# I2C_nRF.net
KiCad netlist of a schematic drawn in EAGLE
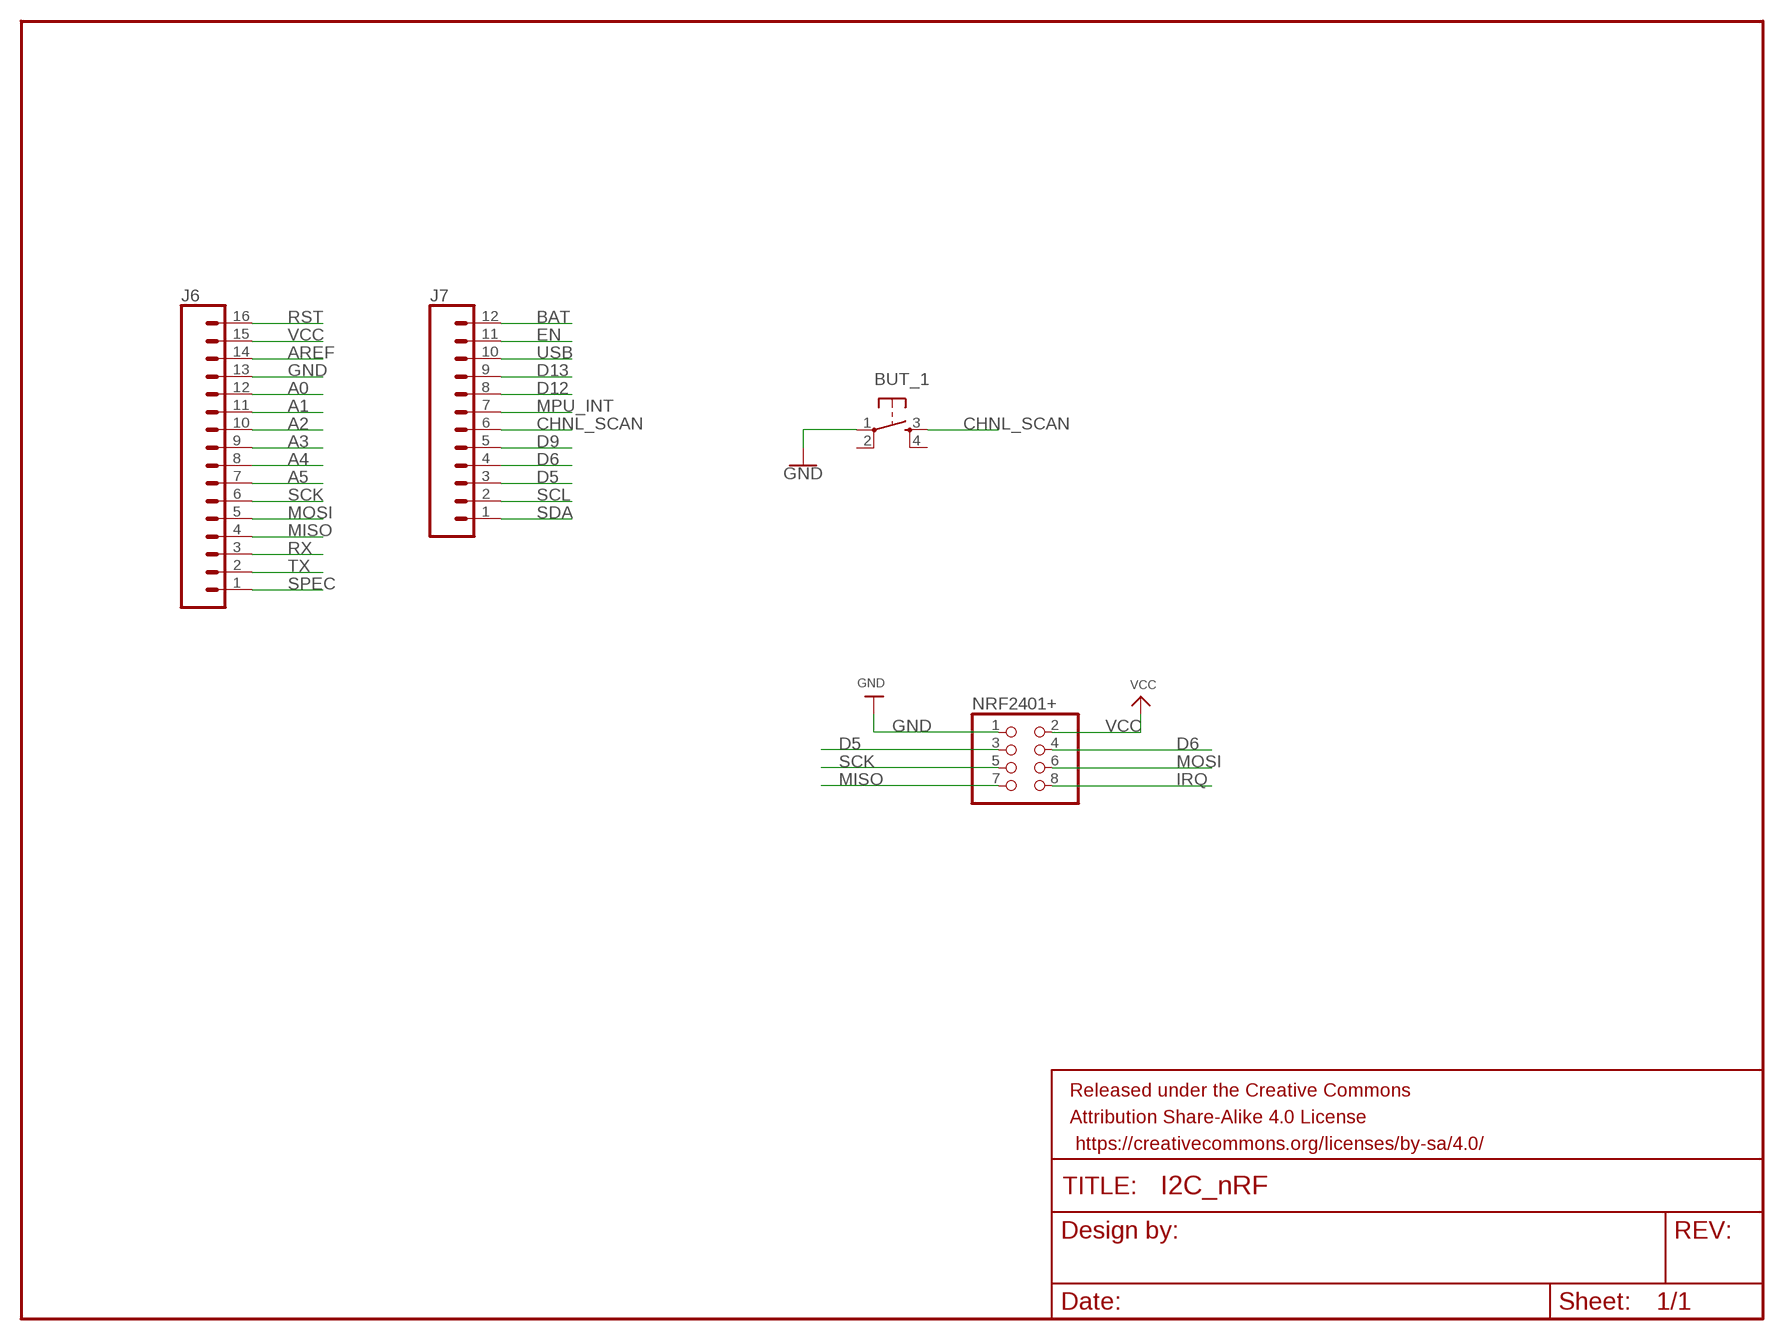
[diagram p0: schematic, sheet 1]

(export (version "E")
  (design (tool "Eeschema 10.0.6"))
  (components
    (comp (ref "BUT_1")
      (value "TAC_SWITCHPTH")
      (footprint "eagle-import:TACTILE-PTH")
      (libsource (lib "eagle-import") (part "TAC_SWITCHPTH"))
    )
    (comp (ref "FRAME1")
      (value "FRAME-LETTER")
      (footprint "eagle-import:CREATIVE_COMMONS")
      (libsource (lib "eagle-import") (part "FRAME-LETTER"))
    )
    (comp (ref "J6")
      (value "CONN_16")
      (footprint "eagle-import:1X16")
      (libsource (lib "eagle-import") (part "CONN_16"))
    )
    (comp (ref "J7")
      (value "CONN_12")
      (footprint "eagle-import:1X12")
      (libsource (lib "eagle-import") (part "CONN_12"))
    )
    (comp (ref "NRF2401+")
      (value "PINHD-2X4")
      (footprint "eagle-import:2X04")
      (libsource (lib "eagle-import") (part "PINHD-2X4"))
    )
  )
  (nets
    (net (code "1") (name "/A0") (class "Default")
      (node (ref "J6") (pin "12") (pinfunction "12_12") (pintype "passive"))
    )
    (net (code "2") (name "/A1") (class "Default")
      (node (ref "J6") (pin "11") (pinfunction "11_11") (pintype "passive"))
    )
    (net (code "3") (name "/A2") (class "Default")
      (node (ref "J6") (pin "10") (pinfunction "10_10") (pintype "passive"))
    )
    (net (code "4") (name "/A3") (class "Default")
      (node (ref "J6") (pin "9") (pinfunction "9_9") (pintype "passive"))
    )
    (net (code "5") (name "/A4") (class "Default")
      (node (ref "J6") (pin "8") (pinfunction "8_8") (pintype "passive"))
    )
    (net (code "6") (name "/A5") (class "Default")
      (node (ref "J6") (pin "7") (pinfunction "7_7") (pintype "passive"))
    )
    (net (code "7") (name "/AREF") (class "Default")
      (node (ref "J6") (pin "14") (pinfunction "14_14") (pintype "passive"))
    )
    (net (code "8") (name "/BAT") (class "Default")
      (node (ref "J7") (pin "12") (pinfunction "12_12") (pintype "passive"))
    )
    (net (code "9") (name "/CHNL_SCAN") (class "Default")
      (node (ref "BUT_1") (pin "3") (pinfunction "3_3") (pintype "passive"))
      (node (ref "J7") (pin "6") (pinfunction "6_6") (pintype "passive"))
    )
    (net (code "10") (name "/D5") (class "Default")
      (node (ref "J7") (pin "3") (pinfunction "3_3") (pintype "passive"))
      (node (ref "NRF2401+") (pin "3") (pinfunction "3_3") (pintype "passive"))
    )
    (net (code "11") (name "/D6") (class "Default")
      (node (ref "J7") (pin "4") (pinfunction "4_4") (pintype "passive"))
      (node (ref "NRF2401+") (pin "4") (pinfunction "4_4") (pintype "passive"))
    )
    (net (code "12") (name "/D9") (class "Default")
      (node (ref "J7") (pin "5") (pinfunction "5_5") (pintype "passive"))
    )
    (net (code "13") (name "/D12") (class "Default")
      (node (ref "J7") (pin "8") (pinfunction "8_8") (pintype "passive"))
    )
    (net (code "14") (name "/D13") (class "Default")
      (node (ref "J7") (pin "9") (pinfunction "9_9") (pintype "passive"))
    )
    (net (code "15") (name "/EN") (class "Default")
      (node (ref "J7") (pin "11") (pinfunction "11_11") (pintype "passive"))
    )
    (net (code "16") (name "/IRQ") (class "Default")
      (node (ref "NRF2401+") (pin "8") (pinfunction "8_8") (pintype "passive"))
    )
    (net (code "17") (name "/MISO") (class "Default")
      (node (ref "J6") (pin "4") (pinfunction "4_4") (pintype "passive"))
      (node (ref "NRF2401+") (pin "7") (pinfunction "7_7") (pintype "passive"))
    )
    (net (code "18") (name "/MOSI") (class "Default")
      (node (ref "J6") (pin "5") (pinfunction "5_5") (pintype "passive"))
      (node (ref "NRF2401+") (pin "6") (pinfunction "6_6") (pintype "passive"))
    )
    (net (code "19") (name "/MPU_INT") (class "Default")
      (node (ref "J7") (pin "7") (pinfunction "7_7") (pintype "passive"))
    )
    (net (code "20") (name "/RST") (class "Default")
      (node (ref "J6") (pin "16") (pinfunction "16_16") (pintype "passive"))
    )
    (net (code "21") (name "/RX") (class "Default")
      (node (ref "J6") (pin "3") (pinfunction "3_3") (pintype "passive"))
    )
    (net (code "22") (name "/SCK") (class "Default")
      (node (ref "J6") (pin "6") (pinfunction "6_6") (pintype "passive"))
      (node (ref "NRF2401+") (pin "5") (pinfunction "5_5") (pintype "passive"))
    )
    (net (code "23") (name "/SCL") (class "Default")
      (node (ref "J7") (pin "2") (pinfunction "2_2") (pintype "passive"))
    )
    (net (code "24") (name "/SDA") (class "Default")
      (node (ref "J7") (pin "1") (pinfunction "1_1") (pintype "passive"))
    )
    (net (code "25") (name "/SPEC") (class "Default")
      (node (ref "J6") (pin "1") (pinfunction "1_1") (pintype "passive"))
    )
    (net (code "26") (name "/TX") (class "Default")
      (node (ref "J6") (pin "2") (pinfunction "2_2") (pintype "passive"))
    )
    (net (code "27") (name "/USB") (class "Default")
      (node (ref "J7") (pin "10") (pinfunction "10_10") (pintype "passive"))
    )
    (net (code "28") (name "GND") (class "Default")
      (node (ref "BUT_1") (pin "1") (pinfunction "1_1") (pintype "passive"))
      (node (ref "J6") (pin "13") (pinfunction "13_13") (pintype "passive"))
      (node (ref "NRF2401+") (pin "1") (pinfunction "1_1") (pintype "passive"))
    )
    (net (code "29") (name "VCC") (class "Default")
      (node (ref "J6") (pin "15") (pinfunction "15_15") (pintype "passive"))
      (node (ref "NRF2401+") (pin "2") (pinfunction "2_2") (pintype "passive"))
    )
    (net (code "30") (name "unconnected-(BUT_1-Pad2)") (class "Default")
      (node (ref "BUT_1") (pin "2") (pinfunction "2_2") (pintype "passive"))
    )
    (net (code "31") (name "unconnected-(BUT_1-Pad4)") (class "Default")
      (node (ref "BUT_1") (pin "4") (pinfunction "4_4") (pintype "passive"))
    )
  )
)
